# aucma_tranfer.net
KiCad netlist of a schematic drawn in Altium Designer
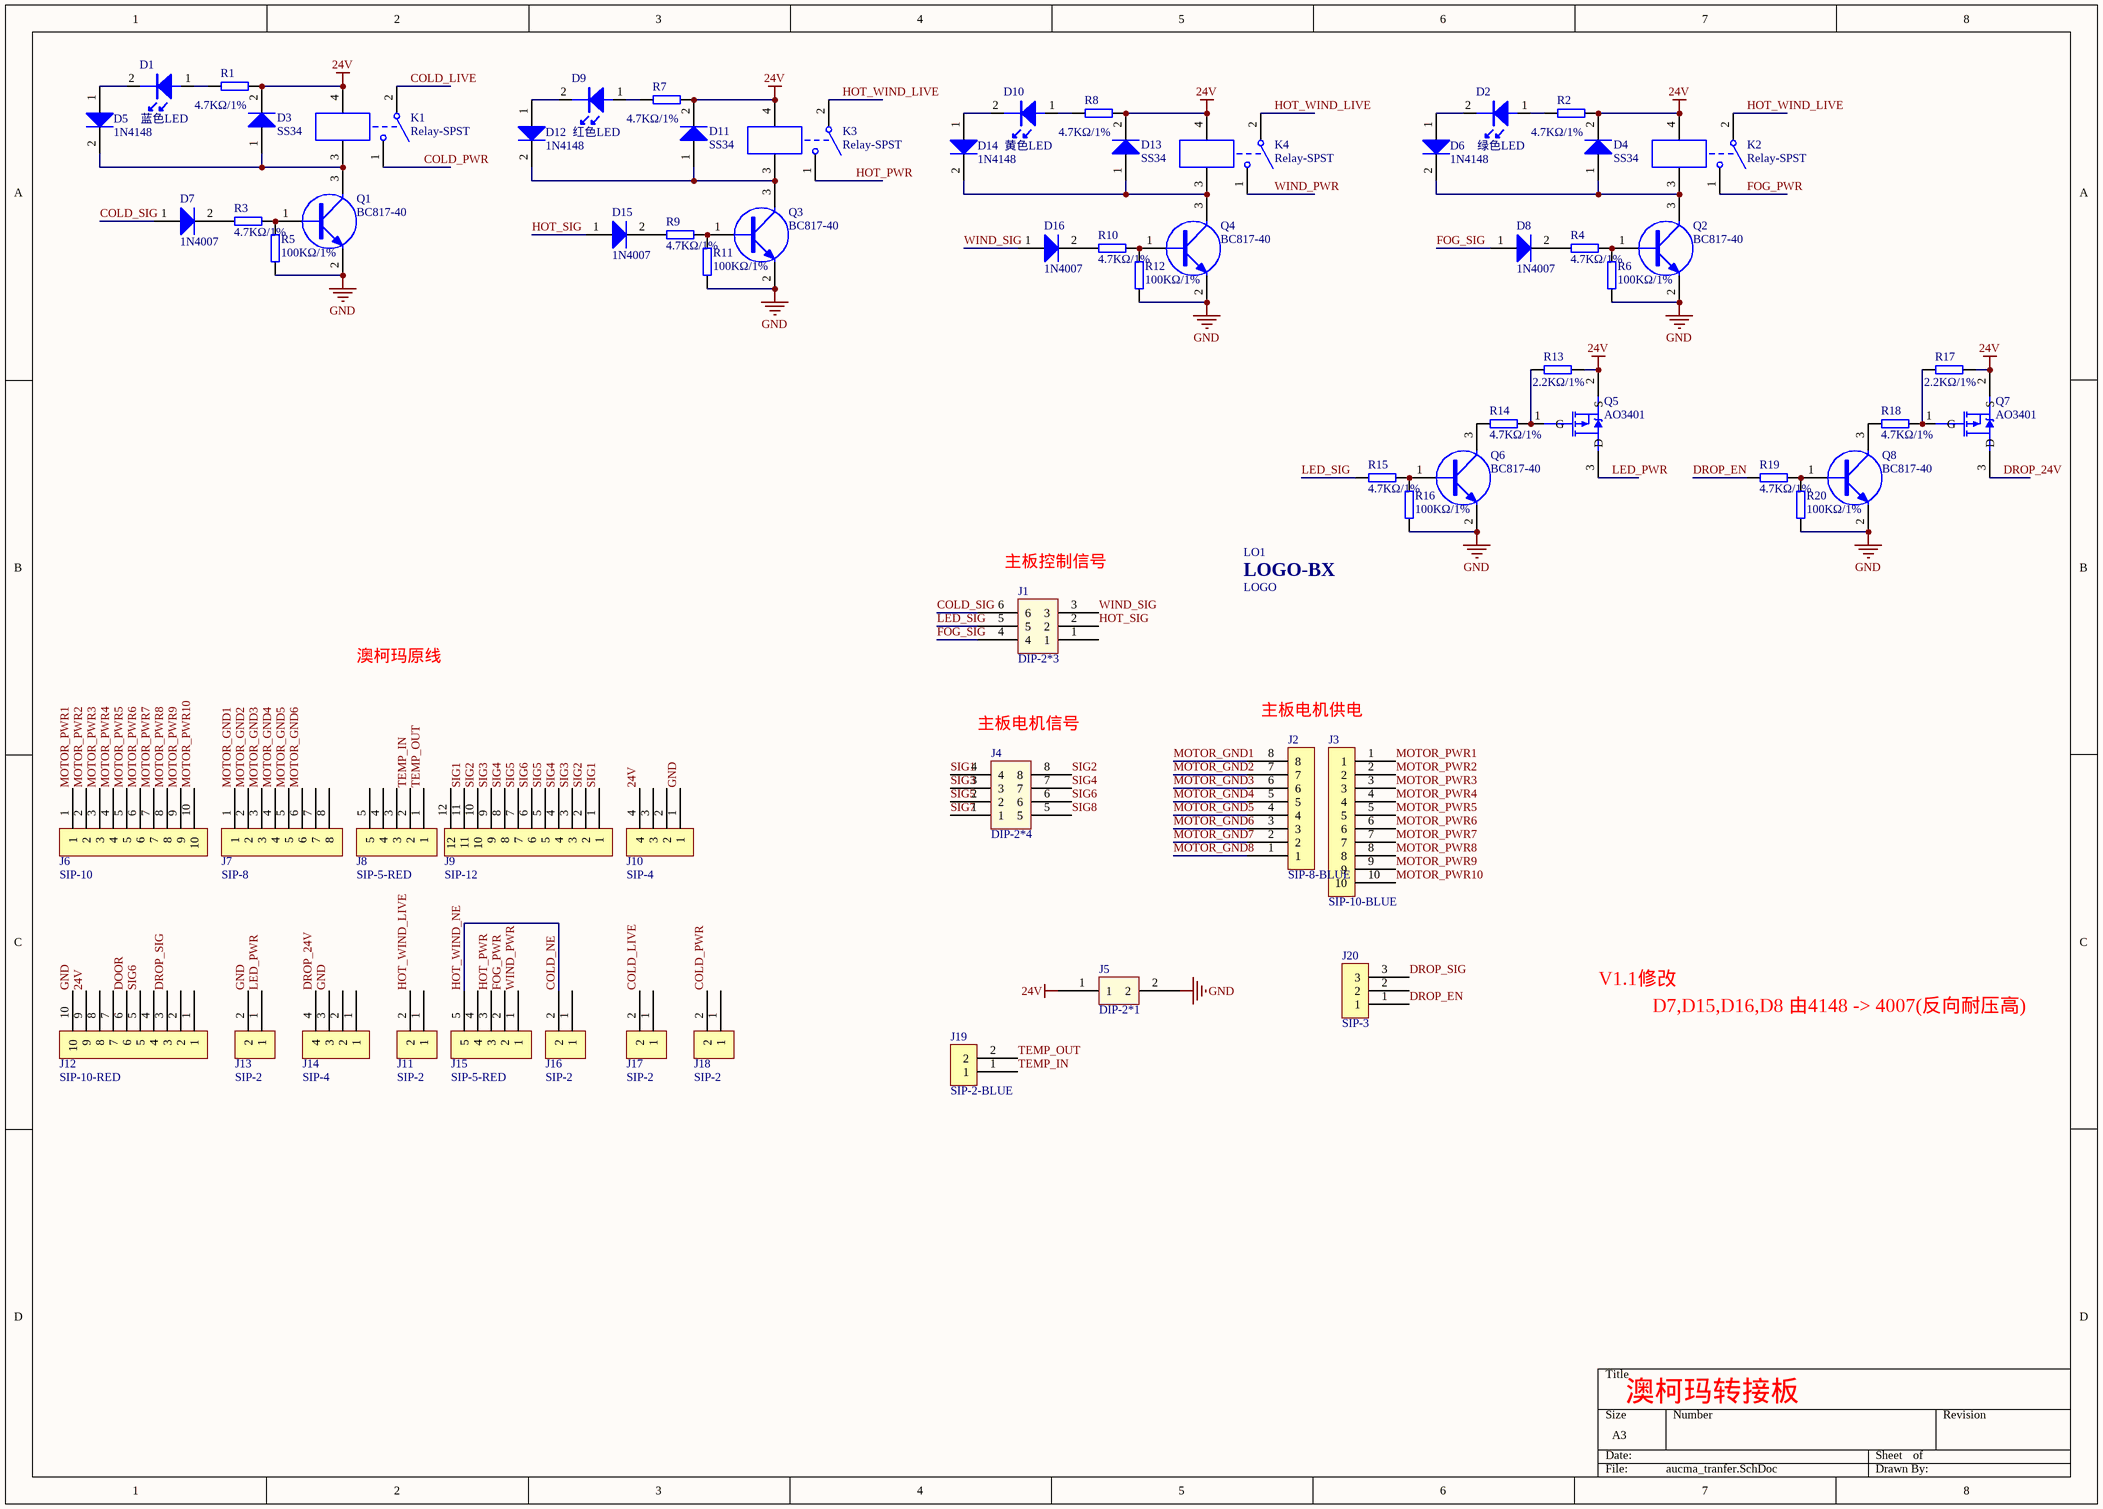
[diagram p0: aucma_tranfer.SchDoc]

(export (version "E")
  (design (tool "Eeschema 10.0.6"))
  (components
    (comp (ref "D1")
      (value "蓝色LED")
      (footprint "0603_D")
      (description "发光二极管")
      (libsource (lib "Integrated_Library") (part "LED"))
    )
    (comp (ref "D2")
      (value "绿色LED")
      (footprint "0603_D")
      (description "发光二极管")
      (libsource (lib "Integrated_Library") (part "LED"))
    )
    (comp (ref "D3")
      (value "SS34")
      (footprint "SMA/DO214AC")
      (description "二极管")
      (libsource (lib "Integrated_Library") (part "Diodes"))
    )
    (comp (ref "D4")
      (value "SS34")
      (footprint "SMA/DO214AC")
      (description "二极管")
      (libsource (lib "Integrated_Library") (part "Diodes"))
    )
    (comp (ref "D5")
      (value "1N4148")
      (footprint "LL34_2P")
      (description "二极管")
      (libsource (lib "Integrated_Library") (part "Diodes"))
    )
    (comp (ref "D6")
      (value "1N4148")
      (footprint "LL34_2P")
      (description "二极管")
      (libsource (lib "Integrated_Library") (part "Diodes"))
    )
    (comp (ref "D7")
      (value "1N4007")
      (footprint "SMA/DO214AC")
      (description "二极管")
      (libsource (lib "Integrated_Library") (part "Diodes"))
    )
    (comp (ref "D8")
      (value "1N4007")
      (footprint "SMA/DO214AC")
      (description "二极管")
      (libsource (lib "Integrated_Library") (part "Diodes"))
    )
    (comp (ref "D9")
      (value "红色LED")
      (footprint "0603_D")
      (description "发光二极管")
      (libsource (lib "Integrated_Library") (part "LED"))
    )
    (comp (ref "D10")
      (value "黄色LED")
      (footprint "0603_D")
      (description "发光二极管")
      (libsource (lib "Integrated_Library") (part "LED"))
    )
    (comp (ref "D11")
      (value "SS34")
      (footprint "SMA/DO214AC")
      (description "二极管")
      (libsource (lib "Integrated_Library") (part "Diodes"))
    )
    (comp (ref "D12")
      (value "1N4148")
      (footprint "LL34_2P")
      (description "二极管")
      (libsource (lib "Integrated_Library") (part "Diodes"))
    )
    (comp (ref "D13")
      (value "SS34")
      (footprint "SMA/DO214AC")
      (description "二极管")
      (libsource (lib "Integrated_Library") (part "Diodes"))
    )
    (comp (ref "D14")
      (value "1N4148")
      (footprint "LL34_2P")
      (description "二极管")
      (libsource (lib "Integrated_Library") (part "Diodes"))
    )
    (comp (ref "D15")
      (value "1N4007")
      (footprint "SMA/DO214AC")
      (description "二极管")
      (libsource (lib "Integrated_Library") (part "Diodes"))
    )
    (comp (ref "D16")
      (value "1N4007")
      (footprint "SMA/DO214AC")
      (description "二极管")
      (libsource (lib "Integrated_Library") (part "Diodes"))
    )
    (comp (ref "J1")
      (value "DIP-2*3")
      (footprint "小5557-2*3A")
      (description "双排2*3P插座")
      (libsource (lib "Integrated_Library") (part "DIP-2*3"))
    )
    (comp (ref "J2")
      (value "SIP-8-BLUE")
      (footprint "XHB-8A")
      (description "单排8P插座")
      (libsource (lib "") (part "SIP-8_1"))
    )
    (comp (ref "J3")
      (value "SIP-10-BLUE")
      (footprint "XHB-10A")
      (description "单排10P插座")
      (libsource (lib "Integrated_Library") (part "SIP-10"))
    )
    (comp (ref "J4")
      (value "DIP-2*4")
      (footprint "PHB-2*4A")
      (description "双排2*4P插座")
      (libsource (lib "Integrated_Library") (part "DIP-2*4"))
    )
    (comp (ref "J5")
      (value "DIP-2*1")
      (footprint "5557-2*1A")
      (description "双排2*1P插座")
      (libsource (lib "Integrated_Library") (part "DIP-2*1"))
    )
    (comp (ref "J6")
      (value "SIP-10")
      (footprint "XHB-10A")
      (description "单排10P插座")
      (libsource (lib "") (part "SIP-10_1"))
    )
    (comp (ref "J7")
      (value "SIP-8")
      (footprint "XHB-8A")
      (description "单排8P插座")
      (libsource (lib "Integrated_Library") (part "SIP-8"))
    )
    (comp (ref "J8")
      (value "SIP-5-RED")
      (footprint "XHB-5A")
      (description "单排5P插座")
      (libsource (lib "Integrated_Library") (part "SIP-5"))
    )
    (comp (ref "J9")
      (value "SIP-12")
      (footprint "XHB-12A")
      (description "单排12P插座")
      (libsource (lib "Integrated_Library") (part "SIP-12"))
    )
    (comp (ref "J10")
      (value "SIP-4")
      (footprint "VH3.96-4A")
      (description "单排4P插座")
      (libsource (lib "Integrated_Library") (part "SIP-4"))
    )
    (comp (ref "J11")
      (value "SIP-2")
      (footprint "positioning crimp terminals")
      (description "单排2P插座")
      (libsource (lib "Integrated_Library") (part "SIP-2"))
    )
    (comp (ref "J12")
      (value "SIP-10-RED")
      (footprint "XHB-10A")
      (description "单排10P插座")
      (libsource (lib "Integrated_Library") (part "SIP-10"))
    )
    (comp (ref "J13")
      (value "SIP-2")
      (footprint "VH3.96-2A")
      (description "单排2P插座")
      (libsource (lib "Integrated_Library") (part "SIP-2"))
    )
    (comp (ref "J14")
      (value "SIP-4")
      (footprint "XHB-4A")
      (description "单排4P插座")
      (libsource (lib "Integrated_Library") (part "SIP-4"))
    )
    (comp (ref "J15")
      (value "SIP-5-RED")
      (footprint "VH3.96-5A")
      (description "单排5P插座")
      (libsource (lib "Integrated_Library") (part "SIP-5"))
    )
    (comp (ref "J16")
      (value "SIP-2")
      (footprint "positioning crimp terminals")
      (description "单排2P插座")
      (libsource (lib "Integrated_Library") (part "SIP-2"))
    )
    (comp (ref "J17")
      (value "SIP-2")
      (footprint "positioning crimp terminals")
      (description "单排2P插座")
      (libsource (lib "Integrated_Library") (part "SIP-2"))
    )
    (comp (ref "J18")
      (value "SIP-2")
      (footprint "positioning crimp terminals")
      (description "单排2P插座")
      (libsource (lib "Integrated_Library") (part "SIP-2"))
    )
    (comp (ref "J19")
      (value "SIP-2-BLUE")
      (footprint "XHB-2A")
      (description "单排2P插座")
      (libsource (lib "") (part "SIP-2_1"))
    )
    (comp (ref "J20")
      (value "SIP-3")
      (footprint "XHB-3A")
      (description "单排3P插座")
      (libsource (lib "Integrated_Library") (part "SIP-3"))
    )
    (comp (ref "K1")
      (value "Relay-SPST")
      (footprint "SLA-24VDC-SL-A")
      (description "继电器 1组常开(单刀单掷)")
      (fields (field (name "PUBLISHER") "Altium Limited"))
      (libsource (lib "Integrated_Library") (part "Relay-SPST"))
    )
    (comp (ref "K2")
      (value "Relay-SPST")
      (footprint "HF152FD-1H")
      (description "继电器 1组常开(单刀单掷)")
      (fields (field (name "PUBLISHER") "Altium Limited"))
      (libsource (lib "Integrated_Library") (part "Relay-SPST"))
    )
    (comp (ref "K3")
      (value "Relay-SPST")
      (footprint "HF152FD-1H")
      (description "继电器 1组常开(单刀单掷)")
      (fields (field (name "PUBLISHER") "Altium Limited"))
      (libsource (lib "Integrated_Library") (part "Relay-SPST"))
    )
    (comp (ref "K4")
      (value "Relay-SPST")
      (footprint "HF152FD-1H")
      (description "继电器 1组常开(单刀单掷)")
      (fields (field (name "PUBLISHER") "Altium Limited"))
      (libsource (lib "Integrated_Library") (part "Relay-SPST"))
    )
    (comp (ref "LO1")
      (value "LOGO")
      (footprint "THAND")
      (description "百兴Logo")
      (libsource (lib "Integrated_Library") (part "LOGO"))
    )
    (comp (ref "Q1")
      (value "BC817-40")
      (footprint "SOT-23-3")
      (description "三极管")
      (libsource (lib "Integrated_Library") (part "NPN"))
    )
    (comp (ref "Q2")
      (value "BC817-40")
      (footprint "SOT-23-3")
      (description "三极管")
      (libsource (lib "Integrated_Library") (part "NPN"))
    )
    (comp (ref "Q3")
      (value "BC817-40")
      (footprint "SOT-23-3")
      (description "三极管")
      (libsource (lib "Integrated_Library") (part "NPN"))
    )
    (comp (ref "Q4")
      (value "BC817-40")
      (footprint "SOT-23-3")
      (description "三极管")
      (libsource (lib "Integrated_Library") (part "NPN"))
    )
    (comp (ref "Q5")
      (value "AO3401")
      (footprint "SOT-23-3")
      (description "P-Channel MOSFET")
      (fields (field (name "PUBLISHER") "Altium Limited"))
      (libsource (lib "Integrated_Library") (part "MOSFET_P"))
    )
    (comp (ref "Q6")
      (value "BC817-40")
      (footprint "SOT-23-3")
      (description "三极管")
      (libsource (lib "Integrated_Library") (part "NPN"))
    )
    (comp (ref "Q7")
      (value "AO3401")
      (footprint "SOT-23-3")
      (description "P-Channel MOSFET")
      (fields (field (name "PUBLISHER") "Altium Limited"))
      (libsource (lib "Integrated_Library") (part "MOSFET_P"))
    )
    (comp (ref "Q8")
      (value "BC817-40")
      (footprint "SOT-23-3")
      (description "三极管")
      (libsource (lib "Integrated_Library") (part "NPN"))
    )
    (comp (ref "R1")
      (value "4.7KΩ/1%")
      (footprint "0805_R")
      (description "电阻")
      (libsource (lib "Integrated_Library") (part "RES2"))
    )
    (comp (ref "R2")
      (value "4.7KΩ/1%")
      (footprint "0805_R")
      (description "电阻")
      (libsource (lib "Integrated_Library") (part "RES2"))
    )
    (comp (ref "R3")
      (value "4.7KΩ/1%")
      (footprint "0603_R")
      (description "电阻")
      (libsource (lib "Integrated_Library") (part "RES2"))
    )
    (comp (ref "R4")
      (value "4.7KΩ/1%")
      (footprint "0603_R")
      (description "电阻")
      (libsource (lib "Integrated_Library") (part "RES2"))
    )
    (comp (ref "R5")
      (value "100KΩ/1%")
      (footprint "0603_R")
      (description "电阻")
      (libsource (lib "Integrated_Library") (part "RES2"))
    )
    (comp (ref "R6")
      (value "100KΩ/1%")
      (footprint "0603_R")
      (description "电阻")
      (libsource (lib "Integrated_Library") (part "RES2"))
    )
    (comp (ref "R7")
      (value "4.7KΩ/1%")
      (footprint "0805_R")
      (description "电阻")
      (libsource (lib "Integrated_Library") (part "RES2"))
    )
    (comp (ref "R8")
      (value "4.7KΩ/1%")
      (footprint "0805_R")
      (description "电阻")
      (libsource (lib "Integrated_Library") (part "RES2"))
    )
    (comp (ref "R9")
      (value "4.7KΩ/1%")
      (footprint "0603_R")
      (description "电阻")
      (libsource (lib "Integrated_Library") (part "RES2"))
    )
    (comp (ref "R10")
      (value "4.7KΩ/1%")
      (footprint "0603_R")
      (description "电阻")
      (libsource (lib "Integrated_Library") (part "RES2"))
    )
    (comp (ref "R11")
      (value "100KΩ/1%")
      (footprint "0603_R")
      (description "电阻")
      (libsource (lib "Integrated_Library") (part "RES2"))
    )
    (comp (ref "R12")
      (value "100KΩ/1%")
      (footprint "0603_R")
      (description "电阻")
      (libsource (lib "Integrated_Library") (part "RES2"))
    )
    (comp (ref "R13")
      (value "2.2KΩ/1%")
      (footprint "0603_R")
      (description "电阻")
      (libsource (lib "Integrated_Library") (part "RES2"))
    )
    (comp (ref "R14")
      (value "4.7KΩ/1%")
      (footprint "0603_R")
      (description "电阻")
      (libsource (lib "Integrated_Library") (part "RES2"))
    )
    (comp (ref "R15")
      (value "4.7KΩ/1%")
      (footprint "0603_R")
      (description "电阻")
      (libsource (lib "Integrated_Library") (part "RES2"))
    )
    (comp (ref "R16")
      (value "100KΩ/1%")
      (footprint "0603_R")
      (description "电阻")
      (libsource (lib "Integrated_Library") (part "RES2"))
    )
    (comp (ref "R17")
      (value "2.2KΩ/1%")
      (footprint "0603_R")
      (description "电阻")
      (libsource (lib "Integrated_Library") (part "RES2"))
    )
    (comp (ref "R18")
      (value "4.7KΩ/1%")
      (footprint "0603_R")
      (description "电阻")
      (libsource (lib "Integrated_Library") (part "RES2"))
    )
    (comp (ref "R19")
      (value "4.7KΩ/1%")
      (footprint "0603_R")
      (description "电阻")
      (libsource (lib "Integrated_Library") (part "RES2"))
    )
    (comp (ref "R20")
      (value "100KΩ/1%")
      (footprint "0603_R")
      (description "电阻")
      (libsource (lib "Integrated_Library") (part "RES2"))
    )
  )
  (nets
    (net (code "1") (name "/COLD_LIVE") (class "Default")
      (node (ref "J17") (pin "2") (pinfunction "2_2") (pintype "passive"))
      (node (ref "K1") (pin "2") (pinfunction "1_2") (pintype "passive"))
    )
    (net (code "2") (name "/COLD_NE") (class "Default")
      (node (ref "J15") (pin "5") (pinfunction "5_5") (pintype "passive"))
      (node (ref "J16") (pin "2") (pinfunction "2_2") (pintype "passive"))
    )
    (net (code "3") (name "/COLD_PWR") (class "Default")
      (node (ref "J18") (pin "2") (pinfunction "2_2") (pintype "passive"))
      (node (ref "K1") (pin "1") (pinfunction "1_1") (pintype "passive"))
    )
    (net (code "4") (name "/COLD_SIG") (class "Default")
      (node (ref "D7") (pin "1") (pinfunction "A_1") (pintype "passive"))
      (node (ref "J1") (pin "6") (pinfunction "6_6") (pintype "passive"))
    )
    (net (code "5") (name "/DOOR") (class "Default")
      (node (ref "J12") (pin "6") (pinfunction "6_6") (pintype "passive"))
    )
    (net (code "6") (name "/DROP_24V") (class "Default")
      (node (ref "J14") (pin "4") (pinfunction "4_4") (pintype "passive"))
      (node (ref "Q7") (pin "3") (pinfunction "D_3") (pintype "passive"))
    )
    (net (code "7") (name "/DROP_EN") (class "Default")
      (node (ref "J20") (pin "1") (pinfunction "1_1") (pintype "passive"))
      (node (ref "R19") (pin "1") (pinfunction "1_1") (pintype "passive"))
    )
    (net (code "8") (name "/DROP_SIG") (class "Default")
      (node (ref "J12") (pin "3") (pinfunction "3_3") (pintype "passive"))
      (node (ref "J20") (pin "3") (pinfunction "3_3") (pintype "passive"))
    )
    (net (code "9") (name "/FOG_PWR") (class "Default")
      (node (ref "J15") (pin "2") (pinfunction "2_2") (pintype "passive"))
      (node (ref "K2") (pin "1") (pinfunction "1_1") (pintype "passive"))
    )
    (net (code "10") (name "/FOG_SIG") (class "Default")
      (node (ref "D8") (pin "1") (pinfunction "A_1") (pintype "passive"))
      (node (ref "J1") (pin "4") (pinfunction "4_4") (pintype "passive"))
    )
    (net (code "11") (name "/HOT_PWR") (class "Default")
      (node (ref "J15") (pin "3") (pinfunction "3_3") (pintype "passive"))
      (node (ref "K3") (pin "1") (pinfunction "1_1") (pintype "passive"))
    )
    (net (code "12") (name "/HOT_SIG") (class "Default")
      (node (ref "D15") (pin "1") (pinfunction "A_1") (pintype "passive"))
      (node (ref "J1") (pin "2") (pinfunction "2_2") (pintype "passive"))
    )
    (net (code "13") (name "/HOT_WIND_LIVE") (class "Default")
      (node (ref "J11") (pin "2") (pinfunction "2_2") (pintype "passive"))
      (node (ref "K2") (pin "2") (pinfunction "1_2") (pintype "passive"))
      (node (ref "K3") (pin "2") (pinfunction "1_2") (pintype "passive"))
      (node (ref "K4") (pin "2") (pinfunction "1_2") (pintype "passive"))
    )
    (net (code "14") (name "/LED_PWR") (class "Default")
      (node (ref "J13") (pin "1") (pinfunction "1_1") (pintype "passive"))
      (node (ref "Q5") (pin "3") (pinfunction "D_3") (pintype "passive"))
    )
    (net (code "15") (name "/LED_SIG") (class "Default")
      (node (ref "J1") (pin "5") (pinfunction "5_5") (pintype "passive"))
      (node (ref "R15") (pin "1") (pinfunction "1_1") (pintype "passive"))
    )
    (net (code "16") (name "/MOTOR_GND1") (class "Default")
      (node (ref "J2") (pin "8") (pinfunction "8_8") (pintype "passive"))
      (node (ref "J7") (pin "1") (pinfunction "1_1") (pintype "passive"))
    )
    (net (code "17") (name "/MOTOR_GND2") (class "Default")
      (node (ref "J2") (pin "7") (pinfunction "7_7") (pintype "passive"))
      (node (ref "J7") (pin "2") (pinfunction "2_2") (pintype "passive"))
    )
    (net (code "18") (name "/MOTOR_GND3") (class "Default")
      (node (ref "J2") (pin "6") (pinfunction "6_6") (pintype "passive"))
      (node (ref "J7") (pin "3") (pinfunction "3_3") (pintype "passive"))
    )
    (net (code "19") (name "/MOTOR_GND4") (class "Default")
      (node (ref "J2") (pin "5") (pinfunction "5_5") (pintype "passive"))
      (node (ref "J7") (pin "4") (pinfunction "4_4") (pintype "passive"))
    )
    (net (code "20") (name "/MOTOR_GND5") (class "Default")
      (node (ref "J2") (pin "4") (pinfunction "4_4") (pintype "passive"))
      (node (ref "J7") (pin "5") (pinfunction "5_5") (pintype "passive"))
    )
    (net (code "21") (name "/MOTOR_GND6") (class "Default")
      (node (ref "J2") (pin "3") (pinfunction "3_3") (pintype "passive"))
      (node (ref "J7") (pin "6") (pinfunction "6_6") (pintype "passive"))
    )
    (net (code "22") (name "/MOTOR_GND7") (class "Default")
      (node (ref "J2") (pin "2") (pinfunction "2_2") (pintype "passive"))
    )
    (net (code "23") (name "/MOTOR_GND8") (class "Default")
      (node (ref "J2") (pin "1") (pinfunction "1_1") (pintype "passive"))
    )
    (net (code "24") (name "/MOTOR_PWR1") (class "Default")
      (node (ref "J3") (pin "1") (pinfunction "1_1") (pintype "passive"))
      (node (ref "J6") (pin "1") (pinfunction "1_1") (pintype "passive"))
    )
    (net (code "25") (name "/MOTOR_PWR2") (class "Default")
      (node (ref "J3") (pin "2") (pinfunction "2_2") (pintype "passive"))
      (node (ref "J6") (pin "2") (pinfunction "2_2") (pintype "passive"))
    )
    (net (code "26") (name "/MOTOR_PWR3") (class "Default")
      (node (ref "J3") (pin "3") (pinfunction "3_3") (pintype "passive"))
      (node (ref "J6") (pin "3") (pinfunction "3_3") (pintype "passive"))
    )
    (net (code "27") (name "/MOTOR_PWR4") (class "Default")
      (node (ref "J3") (pin "4") (pinfunction "4_4") (pintype "passive"))
      (node (ref "J6") (pin "4") (pinfunction "4_4") (pintype "passive"))
    )
    (net (code "28") (name "/MOTOR_PWR5") (class "Default")
      (node (ref "J3") (pin "5") (pinfunction "5_5") (pintype "passive"))
      (node (ref "J6") (pin "5") (pinfunction "5_5") (pintype "passive"))
    )
    (net (code "29") (name "/MOTOR_PWR6") (class "Default")
      (node (ref "J3") (pin "6") (pinfunction "6_6") (pintype "passive"))
      (node (ref "J6") (pin "6") (pinfunction "6_6") (pintype "passive"))
    )
    (net (code "30") (name "/MOTOR_PWR7") (class "Default")
      (node (ref "J3") (pin "7") (pinfunction "7_7") (pintype "passive"))
      (node (ref "J6") (pin "7") (pinfunction "7_7") (pintype "passive"))
    )
    (net (code "31") (name "/MOTOR_PWR8") (class "Default")
      (node (ref "J3") (pin "8") (pinfunction "8_8") (pintype "passive"))
      (node (ref "J6") (pin "8") (pinfunction "8_8") (pintype "passive"))
    )
    (net (code "32") (name "/MOTOR_PWR9") (class "Default")
      (node (ref "J3") (pin "9") (pinfunction "9_9") (pintype "passive"))
      (node (ref "J6") (pin "9") (pinfunction "9_9") (pintype "passive"))
    )
    (net (code "33") (name "/MOTOR_PWR10") (class "Default")
      (node (ref "J3") (pin "10") (pinfunction "10_10") (pintype "passive"))
      (node (ref "J6") (pin "10") (pinfunction "10_10") (pintype "passive"))
    )
    (net (code "34") (name "/SIG1") (class "Default")
      (node (ref "J4") (pin "4") (pinfunction "4_4") (pintype "passive"))
      (node (ref "J9") (pin "1") (pinfunction "1_1") (pintype "passive"))
      (node (ref "J9") (pin "11") (pinfunction "11_11") (pintype "passive"))
    )
    (net (code "35") (name "/SIG2") (class "Default")
      (node (ref "J4") (pin "8") (pinfunction "8_8") (pintype "passive"))
      (node (ref "J9") (pin "10") (pinfunction "10_10") (pintype "passive"))
      (node (ref "J9") (pin "2") (pinfunction "2_2") (pintype "passive"))
    )
    (net (code "36") (name "/SIG3") (class "Default")
      (node (ref "J4") (pin "3") (pinfunction "3_3") (pintype "passive"))
      (node (ref "J9") (pin "3") (pinfunction "3_3") (pintype "passive"))
      (node (ref "J9") (pin "9") (pinfunction "9_9") (pintype "passive"))
    )
    (net (code "37") (name "/SIG4") (class "Default")
      (node (ref "J4") (pin "7") (pinfunction "7_7") (pintype "passive"))
      (node (ref "J9") (pin "4") (pinfunction "4_4") (pintype "passive"))
      (node (ref "J9") (pin "8") (pinfunction "8_8") (pintype "passive"))
    )
    (net (code "38") (name "/SIG5") (class "Default")
      (node (ref "J4") (pin "2") (pinfunction "2_2") (pintype "passive"))
      (node (ref "J9") (pin "5") (pinfunction "5_5") (pintype "passive"))
      (node (ref "J9") (pin "7") (pinfunction "7_7") (pintype "passive"))
    )
    (net (code "39") (name "/SIG6") (class "Default")
      (node (ref "J12") (pin "5") (pinfunction "5_5") (pintype "passive"))
      (node (ref "J4") (pin "6") (pinfunction "6_6") (pintype "passive"))
      (node (ref "J9") (pin "6") (pinfunction "6_6") (pintype "passive"))
    )
    (net (code "40") (name "/SIG7") (class "Default")
      (node (ref "J4") (pin "1") (pinfunction "1_1") (pintype "passive"))
    )
    (net (code "41") (name "/SIG8") (class "Default")
      (node (ref "J4") (pin "5") (pinfunction "5_5") (pintype "passive"))
    )
    (net (code "42") (name "/TEMP_IN") (class "Default")
      (node (ref "J19") (pin "1") (pinfunction "1_1") (pintype "passive"))
      (node (ref "J8") (pin "2") (pinfunction "2_2") (pintype "passive"))
    )
    (net (code "43") (name "/TEMP_OUT") (class "Default")
      (node (ref "J19") (pin "2") (pinfunction "2_2") (pintype "passive"))
      (node (ref "J8") (pin "1") (pinfunction "1_1") (pintype "passive"))
    )
    (net (code "44") (name "/WIND_PWR") (class "Default")
      (node (ref "J15") (pin "1") (pinfunction "1_1") (pintype "passive"))
      (node (ref "K4") (pin "1") (pinfunction "1_1") (pintype "passive"))
    )
    (net (code "45") (name "/WIND_SIG") (class "Default")
      (node (ref "D16") (pin "1") (pinfunction "A_1") (pintype "passive"))
      (node (ref "J1") (pin "3") (pinfunction "3_3") (pintype "passive"))
    )
    (net (code "46") (name "24V") (class "Default")
      (node (ref "D11") (pin "2") (pinfunction "K_2") (pintype "passive"))
      (node (ref "D13") (pin "2") (pinfunction "K_2") (pintype "passive"))
      (node (ref "D3") (pin "2") (pinfunction "K_2") (pintype "passive"))
      (node (ref "D4") (pin "2") (pinfunction "K_2") (pintype "passive"))
      (node (ref "J10") (pin "4") (pinfunction "4_4") (pintype "passive"))
      (node (ref "J12") (pin "9") (pinfunction "9_9") (pintype "passive"))
      (node (ref "J5") (pin "1") (pinfunction "1_1") (pintype "passive"))
      (node (ref "K1") (pin "4") (pinfunction "4_4") (pintype "passive"))
      (node (ref "K2") (pin "4") (pinfunction "4_4") (pintype "passive"))
      (node (ref "K3") (pin "4") (pinfunction "4_4") (pintype "passive"))
      (node (ref "K4") (pin "4") (pinfunction "4_4") (pintype "passive"))
      (node (ref "Q5") (pin "2") (pinfunction "S_2") (pintype "passive"))
      (node (ref "Q7") (pin "2") (pinfunction "S_2") (pintype "passive"))
      (node (ref "R1") (pin "2") (pinfunction "2_2") (pintype "passive"))
      (node (ref "R13") (pin "1") (pinfunction "1_1") (pintype "passive"))
      (node (ref "R17") (pin "1") (pinfunction "1_1") (pintype "passive"))
      (node (ref "R2") (pin "2") (pinfunction "2_2") (pintype "passive"))
      (node (ref "R7") (pin "2") (pinfunction "2_2") (pintype "passive"))
      (node (ref "R8") (pin "2") (pinfunction "2_2") (pintype "passive"))
    )
    (net (code "47") (name "GND") (class "Default")
      (node (ref "J10") (pin "1") (pinfunction "1_1") (pintype "passive"))
      (node (ref "J12") (pin "10") (pinfunction "10_10") (pintype "passive"))
      (node (ref "J13") (pin "2") (pinfunction "2_2") (pintype "passive"))
      (node (ref "J14") (pin "3") (pinfunction "3_3") (pintype "passive"))
      (node (ref "J5") (pin "2") (pinfunction "2_2") (pintype "passive"))
      (node (ref "Q1") (pin "2") (pinfunction "2_2") (pintype "passive"))
      (node (ref "Q2") (pin "2") (pinfunction "2_2") (pintype "passive"))
      (node (ref "Q3") (pin "2") (pinfunction "2_2") (pintype "passive"))
      (node (ref "Q4") (pin "2") (pinfunction "2_2") (pintype "passive"))
      (node (ref "Q6") (pin "2") (pinfunction "2_2") (pintype "passive"))
      (node (ref "Q8") (pin "2") (pinfunction "2_2") (pintype "passive"))
      (node (ref "R11") (pin "1") (pinfunction "1_1") (pintype "passive"))
      (node (ref "R12") (pin "1") (pinfunction "1_1") (pintype "passive"))
      (node (ref "R16") (pin "1") (pinfunction "1_1") (pintype "passive"))
      (node (ref "R20") (pin "1") (pinfunction "1_1") (pintype "passive"))
      (node (ref "R5") (pin "1") (pinfunction "1_1") (pintype "passive"))
      (node (ref "R6") (pin "1") (pinfunction "1_1") (pintype "passive"))
    )
    (net (code "48") (name "Net-(D1-Pad1)") (class "Default")
      (node (ref "D1") (pin "1") (pinfunction "1_1") (pintype "passive"))
      (node (ref "R1") (pin "1") (pinfunction "1_1") (pintype "passive"))
    )
    (net (code "49") (name "Net-(D2-Pad1)") (class "Default")
      (node (ref "D2") (pin "1") (pinfunction "1_1") (pintype "passive"))
      (node (ref "R2") (pin "1") (pinfunction "1_1") (pintype "passive"))
    )
    (net (code "50") (name "Net-(D3-A)") (class "Default")
      (node (ref "D3") (pin "1") (pinfunction "A_1") (pintype "passive"))
      (node (ref "D5") (pin "2") (pinfunction "K_2") (pintype "passive"))
      (node (ref "K1") (pin "3") (pinfunction "5_3") (pintype "passive"))
      (node (ref "Q1") (pin "3") (pinfunction "3_3") (pintype "passive"))
    )
    (net (code "51") (name "Net-(D4-A)") (class "Default")
      (node (ref "D4") (pin "1") (pinfunction "A_1") (pintype "passive"))
      (node (ref "D6") (pin "2") (pinfunction "K_2") (pintype "passive"))
      (node (ref "K2") (pin "3") (pinfunction "5_3") (pintype "passive"))
      (node (ref "Q2") (pin "3") (pinfunction "3_3") (pintype "passive"))
    )
    (net (code "52") (name "Net-(D5-A)") (class "Default")
      (node (ref "D1") (pin "2") (pinfunction "2_2") (pintype "passive"))
      (node (ref "D5") (pin "1") (pinfunction "A_1") (pintype "passive"))
    )
    (net (code "53") (name "Net-(D6-A)") (class "Default")
      (node (ref "D2") (pin "2") (pinfunction "2_2") (pintype "passive"))
      (node (ref "D6") (pin "1") (pinfunction "A_1") (pintype "passive"))
    )
    (net (code "54") (name "Net-(D7-K)") (class "Default")
      (node (ref "D7") (pin "2") (pinfunction "K_2") (pintype "passive"))
      (node (ref "R3") (pin "1") (pinfunction "1_1") (pintype "passive"))
    )
    (net (code "55") (name "Net-(D8-K)") (class "Default")
      (node (ref "D8") (pin "2") (pinfunction "K_2") (pintype "passive"))
      (node (ref "R4") (pin "1") (pinfunction "1_1") (pintype "passive"))
    )
    (net (code "56") (name "Net-(D9-Pad1)") (class "Default")
      (node (ref "D9") (pin "1") (pinfunction "1_1") (pintype "passive"))
      (node (ref "R7") (pin "1") (pinfunction "1_1") (pintype "passive"))
    )
    (net (code "57") (name "Net-(D10-Pad1)") (class "Default")
      (node (ref "D10") (pin "1") (pinfunction "1_1") (pintype "passive"))
      (node (ref "R8") (pin "1") (pinfunction "1_1") (pintype "passive"))
    )
    (net (code "58") (name "Net-(D11-A)") (class "Default")
      (node (ref "D11") (pin "1") (pinfunction "A_1") (pintype "passive"))
      (node (ref "D12") (pin "2") (pinfunction "K_2") (pintype "passive"))
      (node (ref "K3") (pin "3") (pinfunction "5_3") (pintype "passive"))
      (node (ref "Q3") (pin "3") (pinfunction "3_3") (pintype "passive"))
    )
    (net (code "59") (name "Net-(D12-A)") (class "Default")
      (node (ref "D12") (pin "1") (pinfunction "A_1") (pintype "passive"))
      (node (ref "D9") (pin "2") (pinfunction "2_2") (pintype "passive"))
    )
    (net (code "60") (name "Net-(D13-A)") (class "Default")
      (node (ref "D13") (pin "1") (pinfunction "A_1") (pintype "passive"))
      (node (ref "D14") (pin "2") (pinfunction "K_2") (pintype "passive"))
      (node (ref "K4") (pin "3") (pinfunction "5_3") (pintype "passive"))
      (node (ref "Q4") (pin "3") (pinfunction "3_3") (pintype "passive"))
    )
    (net (code "61") (name "Net-(D14-A)") (class "Default")
      (node (ref "D10") (pin "2") (pinfunction "2_2") (pintype "passive"))
      (node (ref "D14") (pin "1") (pinfunction "A_1") (pintype "passive"))
    )
    (net (code "62") (name "Net-(D15-K)") (class "Default")
      (node (ref "D15") (pin "2") (pinfunction "K_2") (pintype "passive"))
      (node (ref "R9") (pin "1") (pinfunction "1_1") (pintype "passive"))
    )
    (net (code "63") (name "Net-(D16-K)") (class "Default")
      (node (ref "D16") (pin "2") (pinfunction "K_2") (pintype "passive"))
      (node (ref "R10") (pin "1") (pinfunction "1_1") (pintype "passive"))
    )
    (net (code "64") (name "Net-(Q1-Pad1)") (class "Default")
      (node (ref "Q1") (pin "1") (pinfunction "1_1") (pintype "passive"))
      (node (ref "R3") (pin "2") (pinfunction "2_2") (pintype "passive"))
      (node (ref "R5") (pin "2") (pinfunction "2_2") (pintype "passive"))
    )
    (net (code "65") (name "Net-(Q2-Pad1)") (class "Default")
      (node (ref "Q2") (pin "1") (pinfunction "1_1") (pintype "passive"))
      (node (ref "R4") (pin "2") (pinfunction "2_2") (pintype "passive"))
      (node (ref "R6") (pin "2") (pinfunction "2_2") (pintype "passive"))
    )
    (net (code "66") (name "Net-(Q3-Pad1)") (class "Default")
      (node (ref "Q3") (pin "1") (pinfunction "1_1") (pintype "passive"))
      (node (ref "R11") (pin "2") (pinfunction "2_2") (pintype "passive"))
      (node (ref "R9") (pin "2") (pinfunction "2_2") (pintype "passive"))
    )
    (net (code "67") (name "Net-(Q4-Pad1)") (class "Default")
      (node (ref "Q4") (pin "1") (pinfunction "1_1") (pintype "passive"))
      (node (ref "R10") (pin "2") (pinfunction "2_2") (pintype "passive"))
      (node (ref "R12") (pin "2") (pinfunction "2_2") (pintype "passive"))
    )
    (net (code "68") (name "Net-(Q5-G)") (class "Default")
      (node (ref "Q5") (pin "1") (pinfunction "G_1") (pintype "passive"))
      (node (ref "R13") (pin "2") (pinfunction "2_2") (pintype "passive"))
      (node (ref "R14") (pin "2") (pinfunction "2_2") (pintype "passive"))
    )
    (net (code "69") (name "Net-(Q6-Pad1)") (class "Default")
      (node (ref "Q6") (pin "1") (pinfunction "1_1") (pintype "passive"))
      (node (ref "R15") (pin "2") (pinfunction "2_2") (pintype "passive"))
      (node (ref "R16") (pin "2") (pinfunction "2_2") (pintype "passive"))
    )
    (net (code "70") (name "Net-(Q6-Pad3)") (class "Default")
      (node (ref "Q6") (pin "3") (pinfunction "3_3") (pintype "passive"))
      (node (ref "R14") (pin "1") (pinfunction "1_1") (pintype "passive"))
    )
    (net (code "71") (name "Net-(Q7-G)") (class "Default")
      (node (ref "Q7") (pin "1") (pinfunction "G_1") (pintype "passive"))
      (node (ref "R17") (pin "2") (pinfunction "2_2") (pintype "passive"))
      (node (ref "R18") (pin "2") (pinfunction "2_2") (pintype "passive"))
    )
    (net (code "72") (name "Net-(Q8-Pad1)") (class "Default")
      (node (ref "Q8") (pin "1") (pinfunction "1_1") (pintype "passive"))
      (node (ref "R19") (pin "2") (pinfunction "2_2") (pintype "passive"))
      (node (ref "R20") (pin "2") (pinfunction "2_2") (pintype "passive"))
    )
    (net (code "73") (name "Net-(Q8-Pad3)") (class "Default")
      (node (ref "Q8") (pin "3") (pinfunction "3_3") (pintype "passive"))
      (node (ref "R18") (pin "1") (pinfunction "1_1") (pintype "passive"))
    )
    (net (code "74") (name "unconnected-(J1-Pad1)") (class "Default")
      (node (ref "J1") (pin "1") (pinfunction "1_1") (pintype "passive"))
    )
    (net (code "75") (name "unconnected-(J7-Pad7)") (class "Default")
      (node (ref "J7") (pin "7") (pinfunction "7_7") (pintype "passive"))
    )
    (net (code "76") (name "unconnected-(J7-Pad8)") (class "Default")
      (node (ref "J7") (pin "8") (pinfunction "8_8") (pintype "passive"))
    )
    (net (code "77") (name "unconnected-(J8-Pad3)") (class "Default")
      (node (ref "J8") (pin "3") (pinfunction "3_3") (pintype "passive"))
    )
    (net (code "78") (name "unconnected-(J8-Pad4)") (class "Default")
      (node (ref "J8") (pin "4") (pinfunction "4_4") (pintype "passive"))
    )
    (net (code "79") (name "unconnected-(J8-Pad5)") (class "Default")
      (node (ref "J8") (pin "5") (pinfunction "5_5") (pintype "passive"))
    )
    (net (code "80") (name "unconnected-(J9-Pad12)") (class "Default")
      (node (ref "J9") (pin "12") (pinfunction "12_12") (pintype "passive"))
    )
    (net (code "81") (name "unconnected-(J10-Pad2)") (class "Default")
      (node (ref "J10") (pin "2") (pinfunction "2_2") (pintype "passive"))
    )
    (net (code "82") (name "unconnected-(J10-Pad3)") (class "Default")
      (node (ref "J10") (pin "3") (pinfunction "3_3") (pintype "passive"))
    )
    (net (code "83") (name "unconnected-(J11-Pad1)") (class "Default")
      (node (ref "J11") (pin "1") (pinfunction "1_1") (pintype "passive"))
    )
    (net (code "84") (name "unconnected-(J12-Pad1)") (class "Default")
      (node (ref "J12") (pin "1") (pinfunction "1_1") (pintype "passive"))
    )
    (net (code "85") (name "unconnected-(J12-Pad2)") (class "Default")
      (node (ref "J12") (pin "2") (pinfunction "2_2") (pintype "passive"))
    )
    (net (code "86") (name "unconnected-(J12-Pad4)") (class "Default")
      (node (ref "J12") (pin "4") (pinfunction "4_4") (pintype "passive"))
    )
    (net (code "87") (name "unconnected-(J12-Pad7)") (class "Default")
      (node (ref "J12") (pin "7") (pinfunction "7_7") (pintype "passive"))
    )
    (net (code "88") (name "unconnected-(J12-Pad8)") (class "Default")
      (node (ref "J12") (pin "8") (pinfunction "8_8") (pintype "passive"))
    )
    (net (code "89") (name "unconnected-(J14-Pad1)") (class "Default")
      (node (ref "J14") (pin "1") (pinfunction "1_1") (pintype "passive"))
    )
    (net (code "90") (name "unconnected-(J14-Pad2)") (class "Default")
      (node (ref "J14") (pin "2") (pinfunction "2_2") (pintype "passive"))
    )
    (net (code "91") (name "unconnected-(J15-Pad4)") (class "Default")
      (node (ref "J15") (pin "4") (pinfunction "4_4") (pintype "passive"))
    )
    (net (code "92") (name "unconnected-(J16-Pad1)") (class "Default")
      (node (ref "J16") (pin "1") (pinfunction "1_1") (pintype "passive"))
    )
    (net (code "93") (name "unconnected-(J17-Pad1)") (class "Default")
      (node (ref "J17") (pin "1") (pinfunction "1_1") (pintype "passive"))
    )
    (net (code "94") (name "unconnected-(J18-Pad1)") (class "Default")
      (node (ref "J18") (pin "1") (pinfunction "1_1") (pintype "passive"))
    )
    (net (code "95") (name "unconnected-(J20-Pad2)") (class "Default")
      (node (ref "J20") (pin "2") (pinfunction "2_2") (pintype "passive"))
    )
  )
)
